# TPS63060.net
KiCad netlist of a schematic drawn in Altium Designer
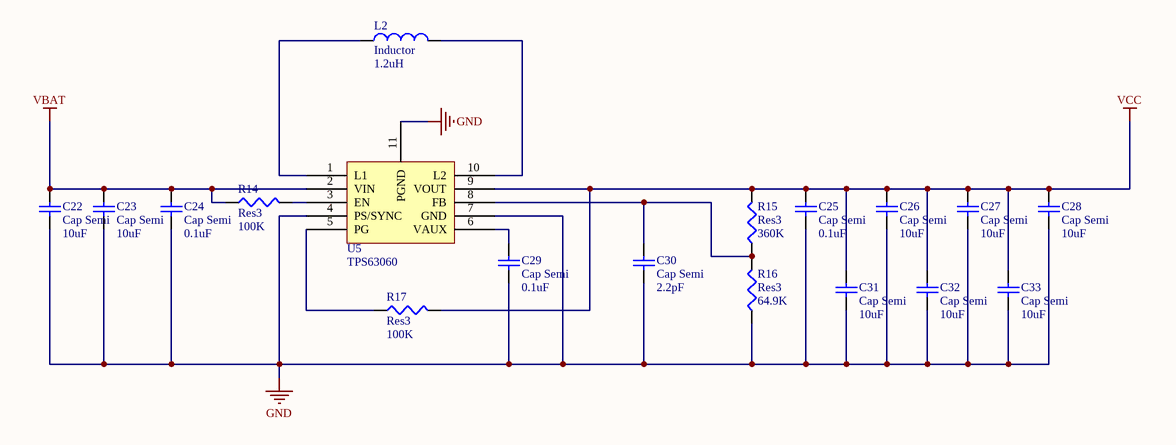
[diagram p0: TPS63060.SchDoc]

(export (version "E")
  (design (tool "Eeschema 10.0.6"))
  (components
    (comp (ref "C22")
      (value "Cap Semi")
      (footprint "1608[0603]")
      (description "Capacitor (Semiconductor SIM Model)")
      (fields (field (name "ALTIUM_VALUE") "10uF") (field (name "PUBLISHER") "Altium Limited"))
      (libsource (lib "Miscellaneous Devices") (part "Cap Semi"))
    )
    (comp (ref "C23")
      (value "Cap Semi")
      (footprint "1608[0603]")
      (description "Capacitor (Semiconductor SIM Model)")
      (fields (field (name "ALTIUM_VALUE") "10uF") (field (name "PUBLISHER") "Altium Limited"))
      (libsource (lib "Miscellaneous Devices") (part "Cap Semi"))
    )
    (comp (ref "C24")
      (value "Cap Semi")
      (footprint "1608[0603]")
      (description "Capacitor (Semiconductor SIM Model)")
      (fields (field (name "ALTIUM_VALUE") "0.1uF") (field (name "PUBLISHER") "Altium Limited"))
      (libsource (lib "Miscellaneous Devices") (part "Cap Semi"))
    )
    (comp (ref "C25")
      (value "Cap Semi")
      (footprint "1608[0603]")
      (description "Capacitor (Semiconductor SIM Model)")
      (fields (field (name "ALTIUM_VALUE") "0.1uF") (field (name "PUBLISHER") "Altium Limited"))
      (libsource (lib "Miscellaneous Devices") (part "Cap Semi"))
    )
    (comp (ref "C26")
      (value "Cap Semi")
      (footprint "1608[0603]")
      (description "Capacitor (Semiconductor SIM Model)")
      (fields (field (name "ALTIUM_VALUE") "10uF") (field (name "PUBLISHER") "Altium Limited"))
      (libsource (lib "Miscellaneous Devices") (part "Cap Semi"))
    )
    (comp (ref "C27")
      (value "Cap Semi")
      (footprint "1608[0603]")
      (description "Capacitor (Semiconductor SIM Model)")
      (fields (field (name "ALTIUM_VALUE") "10uF") (field (name "PUBLISHER") "Altium Limited"))
      (libsource (lib "Miscellaneous Devices") (part "Cap Semi"))
    )
    (comp (ref "C28")
      (value "Cap Semi")
      (footprint "1608[0603]")
      (description "Capacitor (Semiconductor SIM Model)")
      (fields (field (name "ALTIUM_VALUE") "10uF") (field (name "PUBLISHER") "Altium Limited"))
      (libsource (lib "Miscellaneous Devices") (part "Cap Semi"))
    )
    (comp (ref "C29")
      (value "Cap Semi")
      (footprint "1608[0603]")
      (description "Capacitor (Semiconductor SIM Model)")
      (fields (field (name "ALTIUM_VALUE") "0.1uF") (field (name "PUBLISHER") "Altium Limited"))
      (libsource (lib "Miscellaneous Devices") (part "Cap Semi"))
    )
    (comp (ref "C30")
      (value "Cap Semi")
      (footprint "1608[0603]")
      (description "Capacitor (Semiconductor SIM Model)")
      (fields (field (name "ALTIUM_VALUE") "2.2pF") (field (name "PUBLISHER") "Altium Limited"))
      (libsource (lib "Miscellaneous Devices") (part "Cap Semi"))
    )
    (comp (ref "C31")
      (value "Cap Semi")
      (footprint "1608[0603]")
      (description "Capacitor (Semiconductor SIM Model)")
      (fields (field (name "ALTIUM_VALUE") "10uF") (field (name "PUBLISHER") "Altium Limited"))
      (libsource (lib "Miscellaneous Devices") (part "Cap Semi"))
    )
    (comp (ref "C32")
      (value "Cap Semi")
      (footprint "1608[0603]")
      (description "Capacitor (Semiconductor SIM Model)")
      (fields (field (name "ALTIUM_VALUE") "10uF") (field (name "PUBLISHER") "Altium Limited"))
      (libsource (lib "Miscellaneous Devices") (part "Cap Semi"))
    )
    (comp (ref "C33")
      (value "Cap Semi")
      (footprint "1608[0603]")
      (description "Capacitor (Semiconductor SIM Model)")
      (fields (field (name "ALTIUM_VALUE") "10uF") (field (name "PUBLISHER") "Altium Limited"))
      (libsource (lib "Miscellaneous Devices") (part "Cap Semi"))
    )
    (comp (ref "L2")
      (value "Inductor")
      (footprint "INDC4532")
      (fields (field (name "ALTIUM_VALUE") "1.2uH") (field (name "PUBLISHER") "Altium Limited"))
      (libsource (lib "Miscellaneous Devices") (part "Inductor"))
    )
    (comp (ref "R14")
      (value "Res3")
      (footprint "J1-0603")
      (description "Resistor")
      (fields (field (name "ALTIUM_VALUE") "100K") (field (name "PUBLISHER") "Altium Limited"))
      (libsource (lib "Miscellaneous Devices") (part "Res3"))
    )
    (comp (ref "R15")
      (value "Res3")
      (footprint "J1-0603")
      (description "Resistor")
      (fields (field (name "ALTIUM_VALUE") "360K") (field (name "PUBLISHER") "Altium Limited"))
      (libsource (lib "Miscellaneous Devices") (part "Res3"))
    )
    (comp (ref "R16")
      (value "Res3")
      (footprint "J1-0603")
      (description "Resistor")
      (fields (field (name "ALTIUM_VALUE") "64.9K") (field (name "PUBLISHER") "Altium Limited"))
      (libsource (lib "Miscellaneous Devices") (part "Res3"))
    )
    (comp (ref "R17")
      (value "Res3")
      (footprint "J1-0603")
      (description "Resistor")
      (fields (field (name "ALTIUM_VALUE") "100K") (field (name "PUBLISHER") "Altium Limited"))
      (libsource (lib "Miscellaneous Devices") (part "Res3"))
    )
    (comp (ref "U5")
      (value "TPS63060")
      (footprint "S-PSWON-N10")
      (libsource (lib "Custom Parts") (part "TPS63060"))
    )
  )
  (nets
    (net (code "1") (name "GND") (class "Default")
      (node (ref "C22") (pin "1") (pinfunction "1_1") (pintype "passive"))
      (node (ref "C23") (pin "1") (pinfunction "1_1") (pintype "passive"))
      (node (ref "C24") (pin "1") (pinfunction "1_1") (pintype "passive"))
      (node (ref "C25") (pin "1") (pinfunction "1_1") (pintype "passive"))
      (node (ref "C26") (pin "1") (pinfunction "1_1") (pintype "passive"))
      (node (ref "C27") (pin "1") (pinfunction "1_1") (pintype "passive"))
      (node (ref "C28") (pin "1") (pinfunction "1_1") (pintype "passive"))
      (node (ref "C29") (pin "1") (pinfunction "1_1") (pintype "passive"))
      (node (ref "C30") (pin "1") (pinfunction "1_1") (pintype "passive"))
      (node (ref "C31") (pin "1") (pinfunction "1_1") (pintype "passive"))
      (node (ref "C32") (pin "1") (pinfunction "1_1") (pintype "passive"))
      (node (ref "C33") (pin "1") (pinfunction "1_1") (pintype "passive"))
      (node (ref "R16") (pin "1") (pinfunction "1_1") (pintype "passive"))
      (node (ref "U5") (pin "11") (pinfunction "PGND_11") (pintype "passive"))
      (node (ref "U5") (pin "4") (pinfunction "PS/SYNC_4") (pintype "passive"))
      (node (ref "U5") (pin "7") (pinfunction "GND_7") (pintype "passive"))
    )
    (net (code "2") (name "Net-(U5-EN)") (class "Default")
      (node (ref "R14") (pin "2") (pinfunction "2_2") (pintype "passive"))
      (node (ref "U5") (pin "3") (pinfunction "EN_3") (pintype "passive"))
    )
    (net (code "3") (name "Net-(U5-FB)") (class "Default")
      (node (ref "C30") (pin "2") (pinfunction "2_2") (pintype "passive"))
      (node (ref "R15") (pin "1") (pinfunction "1_1") (pintype "passive"))
      (node (ref "R16") (pin "2") (pinfunction "2_2") (pintype "passive"))
      (node (ref "U5") (pin "8") (pinfunction "FB_8") (pintype "passive"))
    )
    (net (code "4") (name "Net-(U5-L1)") (class "Default")
      (node (ref "L2") (pin "1") (pinfunction "1_1") (pintype "passive"))
      (node (ref "U5") (pin "1") (pinfunction "L1_1") (pintype "passive"))
    )
    (net (code "5") (name "Net-(U5-L2)") (class "Default")
      (node (ref "L2") (pin "2") (pinfunction "2_2") (pintype "passive"))
      (node (ref "U5") (pin "10") (pinfunction "L2_10") (pintype "passive"))
    )
    (net (code "6") (name "Net-(U5-PG)") (class "Default")
      (node (ref "R17") (pin "1") (pinfunction "1_1") (pintype "passive"))
      (node (ref "U5") (pin "5") (pinfunction "PG_5") (pintype "passive"))
    )
    (net (code "7") (name "Net-(U5-VAUX)") (class "Default")
      (node (ref "C29") (pin "2") (pinfunction "2_2") (pintype "passive"))
      (node (ref "U5") (pin "6") (pinfunction "VAUX_6") (pintype "passive"))
    )
    (net (code "8") (name "VBAT") (class "Default")
      (node (ref "C22") (pin "2") (pinfunction "2_2") (pintype "passive"))
      (node (ref "C23") (pin "2") (pinfunction "2_2") (pintype "passive"))
      (node (ref "C24") (pin "2") (pinfunction "2_2") (pintype "passive"))
      (node (ref "R14") (pin "1") (pinfunction "1_1") (pintype "passive"))
      (node (ref "U5") (pin "2") (pinfunction "VIN_2") (pintype "passive"))
    )
    (net (code "9") (name "VCC") (class "Default")
      (node (ref "C25") (pin "2") (pinfunction "2_2") (pintype "passive"))
      (node (ref "C26") (pin "2") (pinfunction "2_2") (pintype "passive"))
      (node (ref "C27") (pin "2") (pinfunction "2_2") (pintype "passive"))
      (node (ref "C28") (pin "2") (pinfunction "2_2") (pintype "passive"))
      (node (ref "C31") (pin "2") (pinfunction "2_2") (pintype "passive"))
      (node (ref "C32") (pin "2") (pinfunction "2_2") (pintype "passive"))
      (node (ref "C33") (pin "2") (pinfunction "2_2") (pintype "passive"))
      (node (ref "R15") (pin "2") (pinfunction "2_2") (pintype "passive"))
      (node (ref "R17") (pin "2") (pinfunction "2_2") (pintype "passive"))
      (node (ref "U5") (pin "9") (pinfunction "VOUT_9") (pintype "passive"))
    )
  )
)
